# ST_LINK.net
KiCad netlist of a schematic drawn in Altium Designer
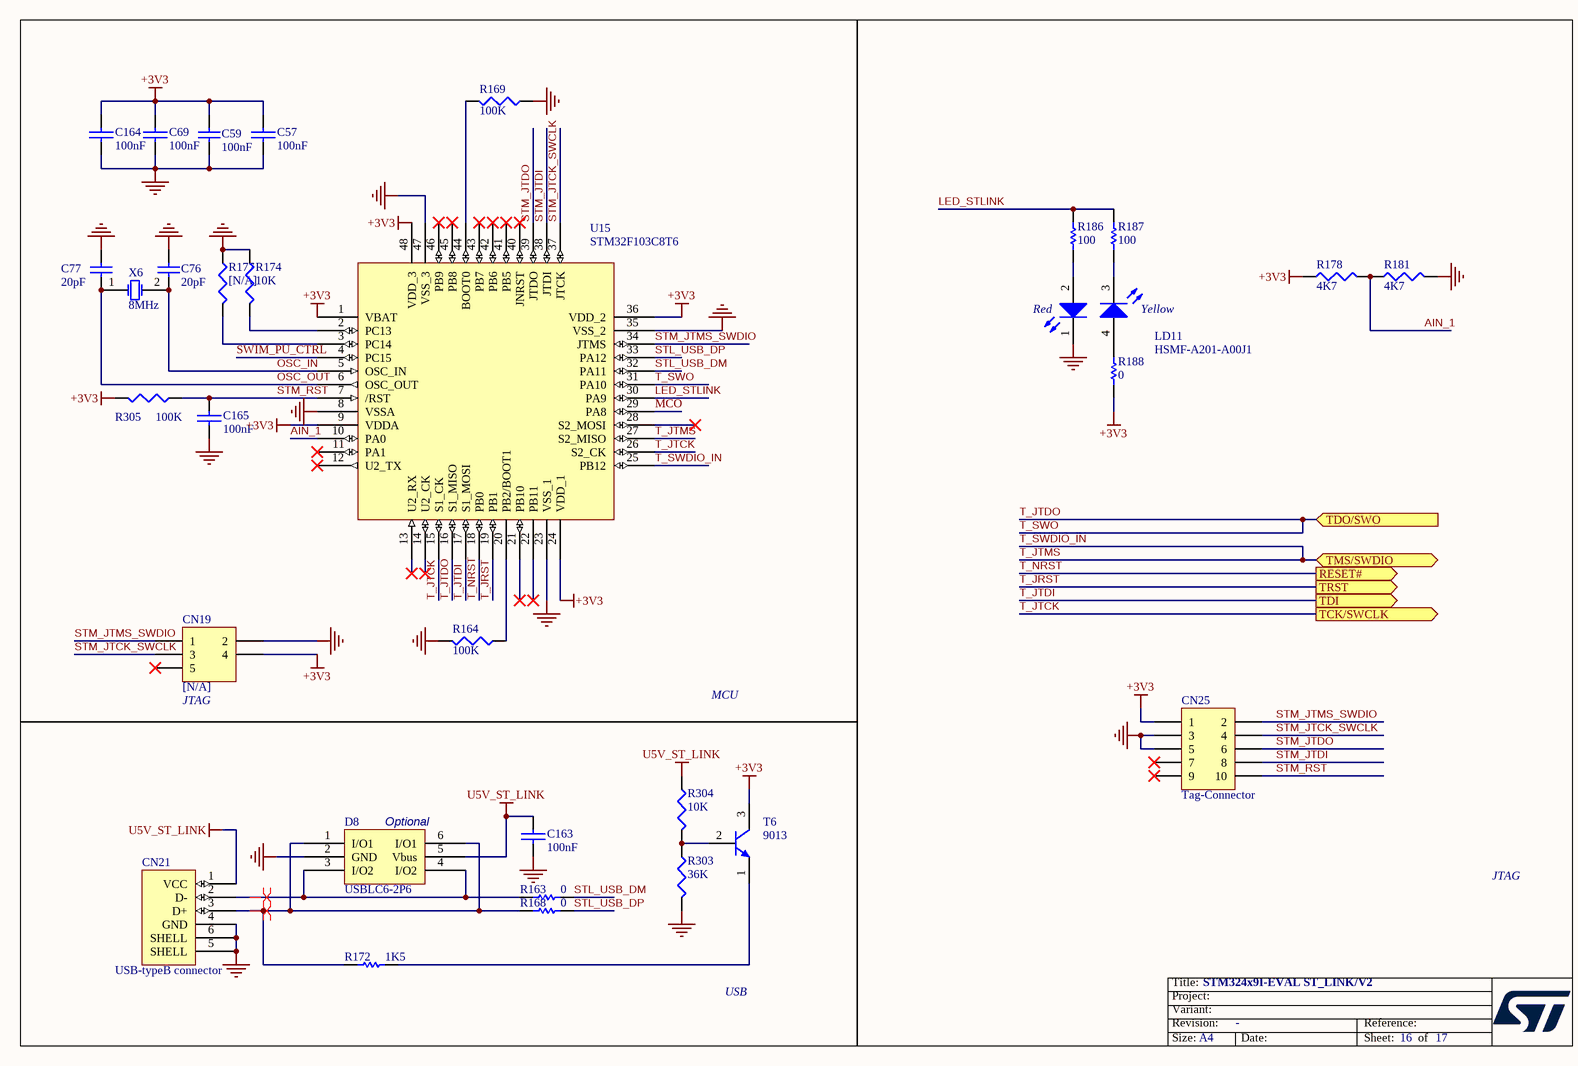
[diagram p0: ST_LINK.SCHDOC]

(export (version "E")
  (design (tool "Eeschema 10.0.6"))
  (components
    (comp (ref "C57") (value "100nF") (footprint "0603C") (libsource (lib "*") (part "CAP")))
    (comp (ref "C59")
      (value "100nF")
      (footprint "0603C")
      (description "Capacitor")
      (fields (field (name "PUBLISHER") "Altium Limited"))
      (libsource (lib "*") (part "Cap"))
    )
    (comp (ref "C69") (value "100nF") (footprint "0603C") (libsource (lib "*") (part "CAP")))
    (comp (ref "C76")
      (value "20pF")
      (footprint "0603C")
      (description "Capacitor")
      (fields (field (name "PUBLISHER") "Altium Limited"))
      (libsource (lib "*") (part "Cap"))
    )
    (comp (ref "C77")
      (value "20pF")
      (footprint "0603C")
      (description "Capacitor")
      (fields (field (name "PUBLISHER") "Altium Limited"))
      (libsource (lib "*") (part "Cap"))
    )
    (comp (ref "C163")
      (value "100nF")
      (footprint "0603C")
      (description "Capacitor")
      (libsource (lib "") (part "CAP_1"))
    )
    (comp (ref "C164") (value "100nF") (footprint "0603C") (libsource (lib "*") (part "CAP")))
    (comp (ref "C165") (value "100nF") (footprint "0603C") (libsource (lib "*") (part "CAP")))
    (comp (ref "CN19")
      (value "[N/A]")
      (footprint "HDR_2X3-1_2R54-6")
      (description "Header, 3-Pin, Dual row")
      (fields (field (name "PUBLISHER") "Altium Limited"))
      (libsource (lib "Miscellaneous Connectors") (part "Header 3X2"))
    )
    (comp (ref "CN21")
      (value "USB-typeB connector")
      (footprint "USB-B")
      (libsource (lib "mb1045") (part "USB-typeB connector"))
    )
    (comp (ref "CN25")
      (value "Tag-Connector")
      (footprint "TC2050-IDC-FP")
      (description "Header, 6-Pin, Dual row")
      (fields (field (name "PUBLISHER") "Altium Limited"))
      (libsource (lib "mb1045") (part "Tag-Connector"))
    )
    (comp (ref "D8") (value "USBLC6-2P6") (footprint "SOT-563") (libsource (lib "mb1045") (part "USBLC6-2")))
    (comp (ref "LD11")
      (value "HSMF-A201-A00J1")
      (footprint "LED2_3528")
      (libsource (lib "MB819") (part "HSMF-A201-A00J1"))
    )
    (comp (ref "R163")
      (value "0")
      (footprint "0603R")
      (description "Resistor")
      (fields (field (name "PUBLISHER") "Altium Limited"))
      (libsource (lib "Miscellaneous Devices") (part "Res1"))
    )
    (comp (ref "R164") (value "100K") (footprint "0603R") (libsource (lib "*") (part "RES1")))
    (comp (ref "R168")
      (value "0")
      (footprint "0603R")
      (description "Resistor")
      (fields (field (name "PUBLISHER") "Altium Limited"))
      (libsource (lib "Miscellaneous Devices") (part "Res1"))
    )
    (comp (ref "R169") (value "100K") (footprint "0603R") (libsource (lib "*") (part "RES1")))
    (comp (ref "R172")
      (value "1K5")
      (footprint "0603R")
      (description "Resistor")
      (fields (field (name "PUBLISHER") "Altium Limited"))
      (libsource (lib "Miscellaneous Devices") (part "Res1"))
    )
    (comp (ref "R174") (value "10K") (footprint "0603R") (libsource (lib "*") (part "R")))
    (comp (ref "R177") (value "[N/A]") (footprint "0603R") (libsource (lib "*") (part "R")))
    (comp (ref "R178") (value "4K7") (footprint "0603R") (libsource (lib "*") (part "RES1")))
    (comp (ref "R181") (value "4K7") (footprint "0603R") (libsource (lib "*") (part "RES1")))
    (comp (ref "R186")
      (value "100")
      (footprint "0603R")
      (description "Resistor")
      (fields (field (name "PUBLISHER") "Altium Limited"))
      (libsource (lib "Miscellaneous Devices") (part "Res1"))
    )
    (comp (ref "R187")
      (value "100")
      (footprint "0603R")
      (description "Resistor")
      (fields (field (name "PUBLISHER") "Altium Limited"))
      (libsource (lib "Miscellaneous Devices") (part "Res1"))
    )
    (comp (ref "R188")
      (value "0")
      (footprint "0603R")
      (description "Resistor")
      (fields (field (name "PUBLISHER") "Altium Limited"))
      (libsource (lib "Miscellaneous Devices") (part "Res1"))
    )
    (comp (ref "R303") (value "36K") (footprint "0603R") (libsource (lib "*") (part "R")))
    (comp (ref "R304") (value "10K") (footprint "0603R") (libsource (lib "*") (part "R")))
    (comp (ref "R305") (value "100K") (footprint "0603R") (libsource (lib "*") (part "RES1")))
    (comp (ref "T6")
      (value "9013")
      (footprint "SOT23-213")
      (description "NPN Bipolar Transistor")
      (fields (field (name "PUBLISHER") "Altium Limited"))
      (libsource (lib "mb1045") (part "NPN"))
    )
    (comp (ref "U15")
      (value "STM32F103C8T6")
      (footprint "LQFP48_0R5_9X9")
      (libsource (lib "*") (part "STM32F10x(48pin)"))
    )
    (comp (ref "X6")
      (value "8MHz")
      (footprint "XTAL_2SM_12R7X4R7")
      (description "Crystal Oscillator")
      (fields (field (name "PUBLISHER") "Altium Limited"))
      (libsource (lib "*") (part "XTAL"))
    )
  )
  (nets
    (net (code "1") (name "+3V3") (class "Default")
      (node (ref "C164") (pin "2") (pinfunction "2_2") (pintype "passive"))
      (node (ref "C57") (pin "2") (pinfunction "2_2") (pintype "passive"))
      (node (ref "C59") (pin "1") (pinfunction "1_1") (pintype "passive"))
      (node (ref "C69") (pin "2") (pinfunction "2_2") (pintype "passive"))
      (node (ref "CN19") (pin "4") (pinfunction "4_4") (pintype "passive"))
      (node (ref "CN25") (pin "1") (pinfunction "1_1") (pintype "passive"))
      (node (ref "R178") (pin "1") (pinfunction "1_1") (pintype "passive"))
      (node (ref "R188") (pin "2") (pinfunction "2_2") (pintype "passive"))
      (node (ref "R305") (pin "2") (pinfunction "2_2") (pintype "passive"))
      (node (ref "T6") (pin "3") (pinfunction "C_3") (pintype "passive"))
      (node (ref "U15") (pin "1") (pinfunction "VBAT_1") (pintype "power_in"))
      (node (ref "U15") (pin "24") (pinfunction "VDD_1_24") (pintype "power_in"))
      (node (ref "U15") (pin "36") (pinfunction "VDD_2_36") (pintype "power_in"))
      (node (ref "U15") (pin "48") (pinfunction "VDD_3_48") (pintype "power_in"))
      (node (ref "U15") (pin "9") (pinfunction "VDDA_9") (pintype "power_in"))
    )
    (net (code "2") (name "/AIN_1") (class "Default")
      (node (ref "R178") (pin "2") (pinfunction "2_2") (pintype "passive"))
      (node (ref "R181") (pin "1") (pinfunction "1_1") (pintype "passive"))
      (node (ref "U15") (pin "10") (pinfunction "PA0_10") (pintype "bidirectional"))
    )
    (net (code "3") (name "/LED_STLINK") (class "Default")
      (node (ref "R186") (pin "1") (pinfunction "1_1") (pintype "passive"))
      (node (ref "R187") (pin "1") (pinfunction "1_1") (pintype "passive"))
      (node (ref "U15") (pin "30") (pinfunction "PA9_30") (pintype "bidirectional"))
    )
    (net (code "4") (name "/MCO") (class "Default")
      (node (ref "U15") (pin "29") (pinfunction "PA8_29") (pintype "bidirectional"))
    )
    (net (code "5") (name "/OSC_IN") (class "Default")
      (node (ref "C76") (pin "2") (pinfunction "2_2") (pintype "passive"))
      (node (ref "U15") (pin "5") (pinfunction "OSC_IN_5") (pintype "input"))
      (node (ref "X6") (pin "2") (pinfunction "OSC2_2") (pintype "passive"))
    )
    (net (code "6") (name "/OSC_OUT") (class "Default")
      (node (ref "C77") (pin "2") (pinfunction "2_2") (pintype "passive"))
      (node (ref "U15") (pin "6") (pinfunction "OSC_OUT_6") (pintype "output"))
      (node (ref "X6") (pin "1") (pinfunction "OSC1_1") (pintype "passive"))
    )
    (net (code "7") (name "/STL_USB_DM") (class "Default")
      (node (ref "R163") (pin "1") (pinfunction "1_1") (pintype "passive"))
      (node (ref "U15") (pin "32") (pinfunction "PA11_32") (pintype "bidirectional"))
    )
    (net (code "8") (name "/STL_USB_DP") (class "Default")
      (node (ref "R168") (pin "1") (pinfunction "1_1") (pintype "passive"))
      (node (ref "U15") (pin "33") (pinfunction "PA12_33") (pintype "bidirectional"))
    )
    (net (code "9") (name "/STM_JTCK_SWCLK") (class "Default")
      (node (ref "CN19") (pin "3") (pinfunction "3_3") (pintype "passive"))
      (node (ref "CN25") (pin "4") (pinfunction "4_4") (pintype "passive"))
      (node (ref "U15") (pin "37") (pinfunction "JTCK_37") (pintype "bidirectional"))
    )
    (net (code "10") (name "/STM_JTDI") (class "Default")
      (node (ref "CN25") (pin "8") (pinfunction "8_8") (pintype "passive"))
      (node (ref "U15") (pin "38") (pinfunction "JTDI_38") (pintype "bidirectional"))
    )
    (net (code "11") (name "/STM_JTDO") (class "Default")
      (node (ref "CN25") (pin "6") (pinfunction "6_6") (pintype "passive"))
      (node (ref "U15") (pin "39") (pinfunction "JTDO_39") (pintype "bidirectional"))
    )
    (net (code "12") (name "/STM_JTMS_SWDIO") (class "Default")
      (node (ref "CN19") (pin "1") (pinfunction "1_1") (pintype "passive"))
      (node (ref "CN25") (pin "2") (pinfunction "2_2") (pintype "passive"))
      (node (ref "U15") (pin "34") (pinfunction "JTMS_34") (pintype "bidirectional"))
    )
    (net (code "13") (name "/STM_RST") (class "Default")
      (node (ref "C165") (pin "2") (pinfunction "2_2") (pintype "passive"))
      (node (ref "CN25") (pin "10") (pinfunction "10_10") (pintype "passive"))
      (node (ref "R305") (pin "1") (pinfunction "1_1") (pintype "passive"))
      (node (ref "U15") (pin "7") (pinfunction "/RST_7") (pintype "input"))
    )
    (net (code "14") (name "/SWIM_PU_CTRL") (class "Default")
      (node (ref "U15") (pin "4") (pinfunction "PC15_4") (pintype "bidirectional"))
    )
    (net (code "15") (name "/T_JRST") (class "Default")
      (node (ref "U15") (pin "19") (pinfunction "PB1_19") (pintype "bidirectional"))
    )
    (net (code "16") (name "/T_JTCK") (class "Default")
      (node (ref "U15") (pin "15") (pinfunction "S1_CK_15") (pintype "bidirectional"))
      (node (ref "U15") (pin "26") (pinfunction "S2_CK_26") (pintype "bidirectional"))
    )
    (net (code "17") (name "/T_JTDI") (class "Default")
      (node (ref "U15") (pin "17") (pinfunction "S1_MOSI_17") (pintype "bidirectional"))
    )
    (net (code "18") (name "/T_JTDO") (class "Default")
      (node (ref "U15") (pin "16") (pinfunction "S1_MISO_16") (pintype "bidirectional"))
      (node (ref "U15") (pin "31") (pinfunction "PA10_31") (pintype "bidirectional"))
    )
    (net (code "19") (name "/T_JTMS") (class "Default")
      (node (ref "U15") (pin "25") (pinfunction "PB12_25") (pintype "bidirectional"))
      (node (ref "U15") (pin "27") (pinfunction "S2_MISO_27") (pintype "bidirectional"))
    )
    (net (code "20") (name "/T_NRST") (class "Default")
      (node (ref "U15") (pin "18") (pinfunction "PB0_18") (pintype "bidirectional"))
    )
    (net (code "21") (name "GND") (class "Default")
      (node (ref "C163") (pin "2") (pinfunction "2_2") (pintype "passive"))
      (node (ref "C164") (pin "1") (pinfunction "1_1") (pintype "passive"))
      (node (ref "C165") (pin "1") (pinfunction "1_1") (pintype "passive"))
      (node (ref "C57") (pin "1") (pinfunction "1_1") (pintype "passive"))
      (node (ref "C59") (pin "2") (pinfunction "2_2") (pintype "passive"))
      (node (ref "C69") (pin "1") (pinfunction "1_1") (pintype "passive"))
      (node (ref "C76") (pin "1") (pinfunction "1_1") (pintype "passive"))
      (node (ref "C77") (pin "1") (pinfunction "1_1") (pintype "passive"))
      (node (ref "CN19") (pin "2") (pinfunction "2_2") (pintype "passive"))
      (node (ref "CN21") (pin "4") (pinfunction "GND_4") (pintype "passive"))
      (node (ref "CN21") (pin "5") (pinfunction "SHELL_5") (pintype "power_in"))
      (node (ref "CN21") (pin "6") (pinfunction "SHELL_6") (pintype "power_in"))
      (node (ref "CN25") (pin "3") (pinfunction "3_3") (pintype "passive"))
      (node (ref "CN25") (pin "5") (pinfunction "5_5") (pintype "passive"))
      (node (ref "D8") (pin "2") (pinfunction "GND_2") (pintype "passive"))
      (node (ref "LD11") (pin "1") (pinfunction "RED_cathode_1") (pintype "passive"))
      (node (ref "R164") (pin "2") (pinfunction "2_2") (pintype "passive"))
      (node (ref "R169") (pin "1") (pinfunction "1_1") (pintype "passive"))
      (node (ref "R174") (pin "1") (pinfunction "1_1") (pintype "passive"))
      (node (ref "R177") (pin "1") (pinfunction "1_1") (pintype "passive"))
      (node (ref "R181") (pin "2") (pinfunction "2_2") (pintype "passive"))
      (node (ref "R303") (pin "2") (pinfunction "2_2") (pintype "passive"))
      (node (ref "U15") (pin "23") (pinfunction "VSS_1_23") (pintype "passive"))
      (node (ref "U15") (pin "35") (pinfunction "VSS_2_35") (pintype "passive"))
      (node (ref "U15") (pin "47") (pinfunction "VSS_3_47") (pintype "passive"))
      (node (ref "U15") (pin "8") (pinfunction "VSSA_8") (pintype "passive"))
    )
    (net (code "22") (name "Net-(CN21-D+)") (class "Default")
      (node (ref "CN21") (pin "3") (pinfunction "D+_3") (pintype "bidirectional"))
      (node (ref "D8") (pin "1") (pinfunction "I/O1_1") (pintype "passive"))
      (node (ref "D8") (pin "6") (pinfunction "I/O1_6") (pintype "passive"))
      (node (ref "R168") (pin "2") (pinfunction "2_2") (pintype "passive"))
      (node (ref "R172") (pin "2") (pinfunction "2_2") (pintype "passive"))
    )
    (net (code "23") (name "Net-(CN21-D-)") (class "Default")
      (node (ref "CN21") (pin "2") (pinfunction "D-_2") (pintype "bidirectional"))
      (node (ref "D8") (pin "3") (pinfunction "I/O2_3") (pintype "passive"))
      (node (ref "D8") (pin "4") (pinfunction "I/O2_4") (pintype "passive"))
      (node (ref "R163") (pin "2") (pinfunction "2_2") (pintype "passive"))
    )
    (net (code "24") (name "Net-(LD11-Red_anode)") (class "Default")
      (node (ref "LD11") (pin "2") (pinfunction "Red_anode_2") (pintype "passive"))
      (node (ref "R186") (pin "2") (pinfunction "2_2") (pintype "passive"))
    )
    (net (code "25") (name "Net-(LD11-YellowGreen_anode)") (class "Default")
      (node (ref "LD11") (pin "4") (pinfunction "YellowGreen_anode_4") (pintype "passive"))
      (node (ref "R188") (pin "1") (pinfunction "1_1") (pintype "passive"))
    )
    (net (code "26") (name "Net-(LD11-YellowGreen_cathode)") (class "Default")
      (node (ref "LD11") (pin "3") (pinfunction "YellowGreen_cathode_3") (pintype "passive"))
      (node (ref "R187") (pin "2") (pinfunction "2_2") (pintype "passive"))
    )
    (net (code "27") (name "Net-(T6-B)") (class "Default")
      (node (ref "R303") (pin "1") (pinfunction "1_1") (pintype "passive"))
      (node (ref "R304") (pin "2") (pinfunction "2_2") (pintype "passive"))
      (node (ref "T6") (pin "2") (pinfunction "B_2") (pintype "passive"))
    )
    (net (code "28") (name "Net-(T6-E)") (class "Default")
      (node (ref "R172") (pin "1") (pinfunction "1_1") (pintype "passive"))
      (node (ref "T6") (pin "1") (pinfunction "E_1") (pintype "passive"))
    )
    (net (code "29") (name "Net-(U15-BOOT0)") (class "Default")
      (node (ref "R169") (pin "2") (pinfunction "2_2") (pintype "passive"))
      (node (ref "U15") (pin "44") (pinfunction "BOOT0_44") (pintype "bidirectional"))
    )
    (net (code "30") (name "Net-(U15-PB2{slash}BOOT1)") (class "Default")
      (node (ref "R164") (pin "1") (pinfunction "1_1") (pintype "passive"))
      (node (ref "U15") (pin "20") (pinfunction "PB2/BOOT1_20") (pintype "passive"))
    )
    (net (code "31") (name "Net-(U15-PC13)") (class "Default")
      (node (ref "R174") (pin "2") (pinfunction "2_2") (pintype "passive"))
      (node (ref "U15") (pin "2") (pinfunction "PC13_2") (pintype "bidirectional"))
    )
    (net (code "32") (name "Net-(U15-PC14)") (class "Default")
      (node (ref "R177") (pin "2") (pinfunction "2_2") (pintype "passive"))
      (node (ref "U15") (pin "3") (pinfunction "PC14_3") (pintype "bidirectional"))
    )
    (net (code "33") (name "U5V_ST_LINK") (class "Default")
      (node (ref "C163") (pin "1") (pinfunction "1_1") (pintype "passive"))
      (node (ref "CN21") (pin "1") (pinfunction "VCC_1") (pintype "bidirectional"))
      (node (ref "D8") (pin "5") (pinfunction "Vbus_5") (pintype "passive"))
      (node (ref "R304") (pin "1") (pinfunction "1_1") (pintype "passive"))
    )
    (net (code "34") (name "unconnected-(CN19-Pad5)") (class "Default")
      (node (ref "CN19") (pin "5") (pinfunction "5_5") (pintype "passive+no_connect"))
    )
    (net (code "35") (name "unconnected-(CN25-Pad7)") (class "Default")
      (node (ref "CN25") (pin "7") (pinfunction "7_7") (pintype "passive+no_connect"))
    )
    (net (code "36") (name "unconnected-(CN25-Pad9)") (class "Default")
      (node (ref "CN25") (pin "9") (pinfunction "9_9") (pintype "passive+no_connect"))
    )
    (net (code "37") (name "unconnected-(U15-JNRST-Pad40)") (class "Default")
      (node (ref "U15") (pin "40") (pinfunction "JNRST_40") (pintype "bidirectional+no_connect"))
    )
    (net (code "38") (name "unconnected-(U15-PA1-Pad11)") (class "Default")
      (node (ref "U15") (pin "11") (pinfunction "PA1_11") (pintype "bidirectional+no_connect"))
    )
    (net (code "39") (name "unconnected-(U15-PB5-Pad41)") (class "Default")
      (node (ref "U15") (pin "41") (pinfunction "PB5_41") (pintype "bidirectional+no_connect"))
    )
    (net (code "40") (name "unconnected-(U15-PB6-Pad42)") (class "Default")
      (node (ref "U15") (pin "42") (pinfunction "PB6_42") (pintype "bidirectional+no_connect"))
    )
    (net (code "41") (name "unconnected-(U15-PB7-Pad43)") (class "Default")
      (node (ref "U15") (pin "43") (pinfunction "PB7_43") (pintype "bidirectional+no_connect"))
    )
    (net (code "42") (name "unconnected-(U15-PB8-Pad45)") (class "Default")
      (node (ref "U15") (pin "45") (pinfunction "PB8_45") (pintype "bidirectional+no_connect"))
    )
    (net (code "43") (name "unconnected-(U15-PB9-Pad46)") (class "Default")
      (node (ref "U15") (pin "46") (pinfunction "PB9_46") (pintype "bidirectional+no_connect"))
    )
    (net (code "44") (name "unconnected-(U15-PB10-Pad21)") (class "Default")
      (node (ref "U15") (pin "21") (pinfunction "PB10_21") (pintype "bidirectional+no_connect"))
    )
    (net (code "45") (name "unconnected-(U15-PB11-Pad22)") (class "Default")
      (node (ref "U15") (pin "22") (pinfunction "PB11_22") (pintype "passive+no_connect"))
    )
    (net (code "46") (name "unconnected-(U15-S2_MOSI-Pad28)") (class "Default")
      (node (ref "U15") (pin "28") (pinfunction "S2_MOSI_28") (pintype "bidirectional+no_connect"))
    )
    (net (code "47") (name "unconnected-(U15-U2_CK-Pad14)") (class "Default")
      (node (ref "U15") (pin "14") (pinfunction "U2_CK_14") (pintype "bidirectional+no_connect"))
    )
    (net (code "48") (name "unconnected-(U15-U2_RX-Pad13)") (class "Default")
      (node (ref "U15") (pin "13") (pinfunction "U2_RX_13") (pintype "input+no_connect"))
    )
    (net (code "49") (name "unconnected-(U15-U2_TX-Pad12)") (class "Default")
      (node (ref "U15") (pin "12") (pinfunction "U2_TX_12") (pintype "output+no_connect"))
    )
  )
)
